# obc-v2_DEBUG.net
KiCad netlist of a schematic drawn in Altium Designer
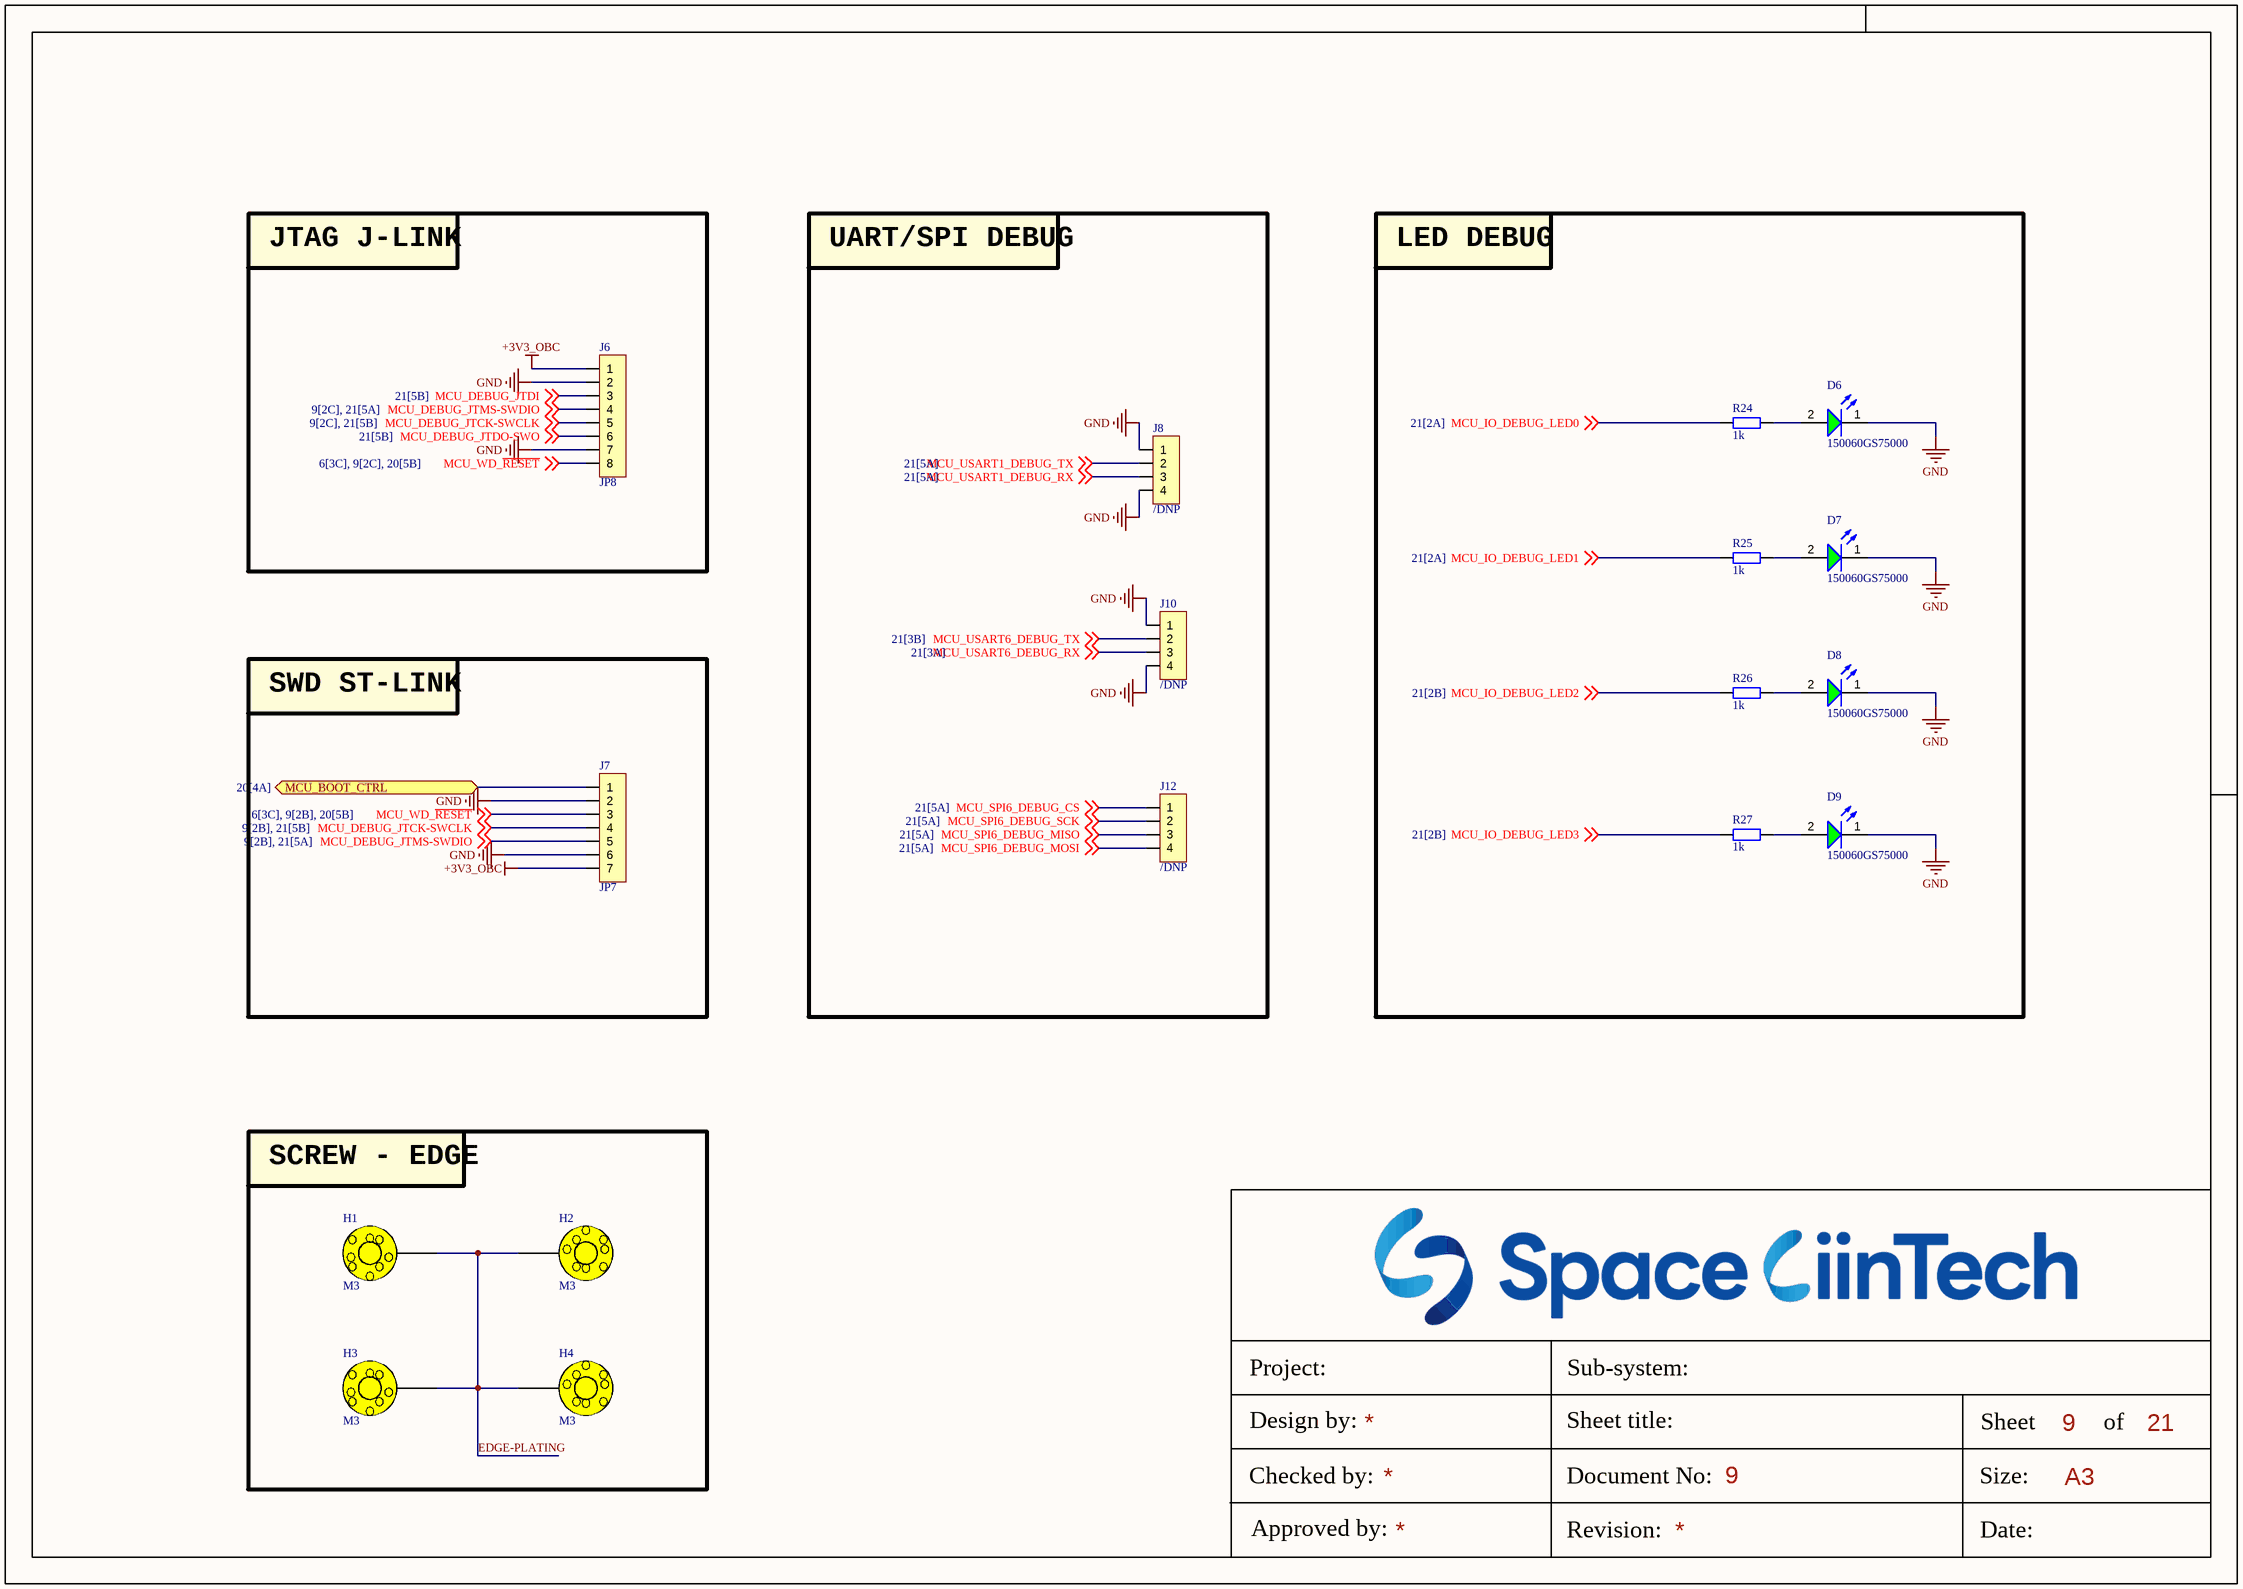
[diagram p0: obc-v2_DEBUG.SchDoc]

(export (version "E")
  (design (tool "Eeschema 10.0.6"))
  (components
    (comp (ref "D6")
      (value "150060GS75000")
      (footprint "WL-SMCW_0603_150060xx75000")
      (description "430mcd Colorless transparence 520nm Emerald 140° LED0603 Light Emitting Diodes (LED) ROHS")
      (libsource (lib "Altium Content Vault") (part "LED_Green_2A-1K"))
    )
    (comp (ref "D7")
      (value "150060GS75000")
      (footprint "WL-SMCW_0603_150060xx75000")
      (description "430mcd Colorless transparence 520nm Emerald 140° LED0603 Light Emitting Diodes (LED) ROHS")
      (libsource (lib "Altium Content Vault") (part "LED_Green_2A-1K"))
    )
    (comp (ref "D8")
      (value "150060GS75000")
      (footprint "WL-SMCW_0603_150060xx75000")
      (description "430mcd Colorless transparence 520nm Emerald 140° LED0603 Light Emitting Diodes (LED) ROHS")
      (libsource (lib "Altium Content Vault") (part "LED_Green_2A-1K"))
    )
    (comp (ref "D9")
      (value "150060GS75000")
      (footprint "WL-SMCW_0603_150060xx75000")
      (description "430mcd Colorless transparence 520nm Emerald 140° LED0603 Light Emitting Diodes (LED) ROHS")
      (libsource (lib "Altium Content Vault") (part "LED_Green_2A-1K"))
    )
    (comp (ref "H1") (value "M3") (footprint "HEX-M3") (libsource (lib "hex_M3") (part "HEX-M3")))
    (comp (ref "H2") (value "M3") (footprint "HEX-M3") (libsource (lib "hex_M3") (part "HEX-M3")))
    (comp (ref "H3") (value "M3") (footprint "HEX-M3") (libsource (lib "hex_M3") (part "HEX-M3")))
    (comp (ref "H4") (value "M3") (footprint "HEX-M3") (libsource (lib "hex_M3") (part "HEX-M3")))
    (comp (ref "J6") (value "JP8") (footprint "JP8-C1T") (libsource (lib "obc_ver2") (part "JP8")))
    (comp (ref "J7") (value "JP7") (footprint "JP7-C1T") (libsource (lib "obc_ver2") (part "JP7")))
    (comp (ref "J8")
      (value "/DNP")
      (footprint "JP4-C1T")
      (description "WR-PHD 2.54 mm Angled Socket Header")
      (fields
        (field (name "MANUFACTURER") "Würth Elektronik eiSos GmbH")
        (field (name "PARTNO") "613004143121")
        (field (name "CREATED BY") "Karrer Zheng")
      )
      (libsource (lib "TechMT.VN_Lib_Project v2") (part "JP4"))
    )
    (comp (ref "J10")
      (value "/DNP")
      (footprint "JP4-C1T")
      (description "WR-PHD 2.54 mm Angled Socket Header")
      (fields
        (field (name "MANUFACTURER") "Würth Elektronik eiSos GmbH")
        (field (name "PARTNO") "613004143121")
        (field (name "CREATED BY") "Karrer Zheng")
      )
      (libsource (lib "TechMT.VN_Lib_Project v2") (part "JP4"))
    )
    (comp (ref "J12")
      (value "/DNP")
      (footprint "JP4-C1T")
      (description "WR-PHD 2.54 mm Angled Socket Header")
      (fields
        (field (name "MANUFACTURER") "Würth Elektronik eiSos GmbH")
        (field (name "PARTNO") "613004143121")
        (field (name "CREATED BY") "Karrer Zheng")
      )
      (libsource (lib "TechMT.VN_Lib_Project v2") (part "JP4"))
    )
    (comp (ref "R24")
      (value "1k")
      (footprint "RES_C_1608X60")
      (description "RES")
      (libsource (lib "Altium_Lib_by_KhueNguyenCreator") (part "Tro 0603 1% 10k"))
    )
    (comp (ref "R25")
      (value "1k")
      (footprint "RES_C_1608X60")
      (description "RES")
      (libsource (lib "Altium_Lib_by_KhueNguyenCreator") (part "Tro 0603 1% 10k"))
    )
    (comp (ref "R26")
      (value "1k")
      (footprint "RES_C_1608X60")
      (description "RES")
      (libsource (lib "Altium_Lib_by_KhueNguyenCreator") (part "Tro 0603 1% 10k"))
    )
    (comp (ref "R27")
      (value "1k")
      (footprint "RES_C_1608X60")
      (description "RES")
      (libsource (lib "Altium_Lib_by_KhueNguyenCreator") (part "Tro 0603 1% 10k"))
    )
  )
  (nets
    (net (code "1") (name "+3V3_OBC") (class "Default")
      (node (ref "J6") (pin "1") (pinfunction "1_1") (pintype "passive"))
      (node (ref "J7") (pin "7") (pinfunction "7_7") (pintype "passive"))
    )
    (net (code "2") (name "/EDGE-PLATING") (class "Default")
      (node (ref "H1") (pin "1") (pinfunction "1_1") (pintype "power_in"))
      (node (ref "H2") (pin "1") (pinfunction "1_1") (pintype "power_in"))
      (node (ref "H3") (pin "1") (pinfunction "1_1") (pintype "power_in"))
      (node (ref "H4") (pin "1") (pinfunction "1_1") (pintype "power_in"))
    )
    (net (code "3") (name "/MCU_BOOT_CTRL") (class "Default")
      (node (ref "J7") (pin "1") (pinfunction "1_1") (pintype "passive"))
    )
    (net (code "4") (name "GND") (class "Default")
      (node (ref "D6") (pin "1") (pinfunction "K_1") (pintype "passive"))
      (node (ref "D7") (pin "1") (pinfunction "K_1") (pintype "passive"))
      (node (ref "D8") (pin "1") (pinfunction "K_1") (pintype "passive"))
      (node (ref "D9") (pin "1") (pinfunction "K_1") (pintype "passive"))
      (node (ref "J10") (pin "1") (pinfunction "1_1") (pintype "passive"))
      (node (ref "J10") (pin "4") (pinfunction "4_4") (pintype "passive"))
      (node (ref "J6") (pin "2") (pinfunction "2_2") (pintype "passive"))
      (node (ref "J6") (pin "7") (pinfunction "7_7") (pintype "passive"))
      (node (ref "J7") (pin "2") (pinfunction "2_2") (pintype "passive"))
      (node (ref "J7") (pin "6") (pinfunction "6_6") (pintype "passive"))
      (node (ref "J8") (pin "1") (pinfunction "1_1") (pintype "passive"))
      (node (ref "J8") (pin "4") (pinfunction "4_4") (pintype "passive"))
    )
    (net (code "5") (name "MCU_DEBUG_JTCK-SWCLK") (class "Default")
      (node (ref "J6") (pin "5") (pinfunction "5_5") (pintype "passive"))
      (node (ref "J7") (pin "4") (pinfunction "4_4") (pintype "passive"))
    )
    (net (code "6") (name "MCU_DEBUG_JTDI") (class "Default")
      (node (ref "J6") (pin "3") (pinfunction "3_3") (pintype "passive"))
    )
    (net (code "7") (name "MCU_DEBUG_JTDO-SWO") (class "Default")
      (node (ref "J6") (pin "6") (pinfunction "6_6") (pintype "passive"))
    )
    (net (code "8") (name "MCU_DEBUG_JTMS-SWDIO") (class "Default")
      (node (ref "J6") (pin "4") (pinfunction "4_4") (pintype "passive"))
      (node (ref "J7") (pin "5") (pinfunction "5_5") (pintype "passive"))
    )
    (net (code "9") (name "MCU_IO_DEBUG_LED0") (class "Default")
      (node (ref "R24") (pin "2") (pinfunction "2_2") (pintype "passive"))
    )
    (net (code "10") (name "MCU_IO_DEBUG_LED1") (class "Default")
      (node (ref "R25") (pin "2") (pinfunction "2_2") (pintype "passive"))
    )
    (net (code "11") (name "MCU_IO_DEBUG_LED2") (class "Default")
      (node (ref "R26") (pin "2") (pinfunction "2_2") (pintype "passive"))
    )
    (net (code "12") (name "MCU_IO_DEBUG_LED3") (class "Default")
      (node (ref "R27") (pin "2") (pinfunction "2_2") (pintype "passive"))
    )
    (net (code "13") (name "MCU_SPI6_DEBUG_CS") (class "Default")
      (node (ref "J12") (pin "1") (pinfunction "1_1") (pintype "passive"))
    )
    (net (code "14") (name "MCU_SPI6_DEBUG_MISO") (class "Default")
      (node (ref "J12") (pin "3") (pinfunction "3_3") (pintype "passive"))
    )
    (net (code "15") (name "MCU_SPI6_DEBUG_MOSI") (class "Default")
      (node (ref "J12") (pin "4") (pinfunction "4_4") (pintype "passive"))
    )
    (net (code "16") (name "MCU_SPI6_DEBUG_SCK") (class "Default")
      (node (ref "J12") (pin "2") (pinfunction "2_2") (pintype "passive"))
    )
    (net (code "17") (name "MCU_USART1_DEBUG_RX") (class "Default")
      (node (ref "J8") (pin "3") (pinfunction "3_3") (pintype "passive"))
    )
    (net (code "18") (name "MCU_USART1_DEBUG_TX") (class "Default")
      (node (ref "J8") (pin "2") (pinfunction "2_2") (pintype "passive"))
    )
    (net (code "19") (name "MCU_USART6_DEBUG_RX") (class "Default")
      (node (ref "J10") (pin "3") (pinfunction "3_3") (pintype "passive"))
    )
    (net (code "20") (name "MCU_USART6_DEBUG_TX") (class "Default")
      (node (ref "J10") (pin "2") (pinfunction "2_2") (pintype "passive"))
    )
    (net (code "21") (name "MCU_WD_~{RESET}") (class "Default")
      (node (ref "J6") (pin "8") (pinfunction "8_8") (pintype "passive"))
      (node (ref "J7") (pin "3") (pinfunction "3_3") (pintype "passive"))
    )
    (net (code "22") (name "Net-(D6-A)") (class "Default")
      (node (ref "D6") (pin "2") (pinfunction "A_2") (pintype "passive"))
      (node (ref "R24") (pin "1") (pinfunction "1_1") (pintype "passive"))
    )
    (net (code "23") (name "Net-(D7-A)") (class "Default")
      (node (ref "D7") (pin "2") (pinfunction "A_2") (pintype "passive"))
      (node (ref "R25") (pin "1") (pinfunction "1_1") (pintype "passive"))
    )
    (net (code "24") (name "Net-(D8-A)") (class "Default")
      (node (ref "D8") (pin "2") (pinfunction "A_2") (pintype "passive"))
      (node (ref "R26") (pin "1") (pinfunction "1_1") (pintype "passive"))
    )
    (net (code "25") (name "Net-(D9-A)") (class "Default")
      (node (ref "D9") (pin "2") (pinfunction "A_2") (pintype "passive"))
      (node (ref "R27") (pin "1") (pinfunction "1_1") (pintype "passive"))
    )
  )
)
